# OpenPLCv0_2_0_USBSwitch.net
KiCad netlist of a schematic drawn in Altium Designer
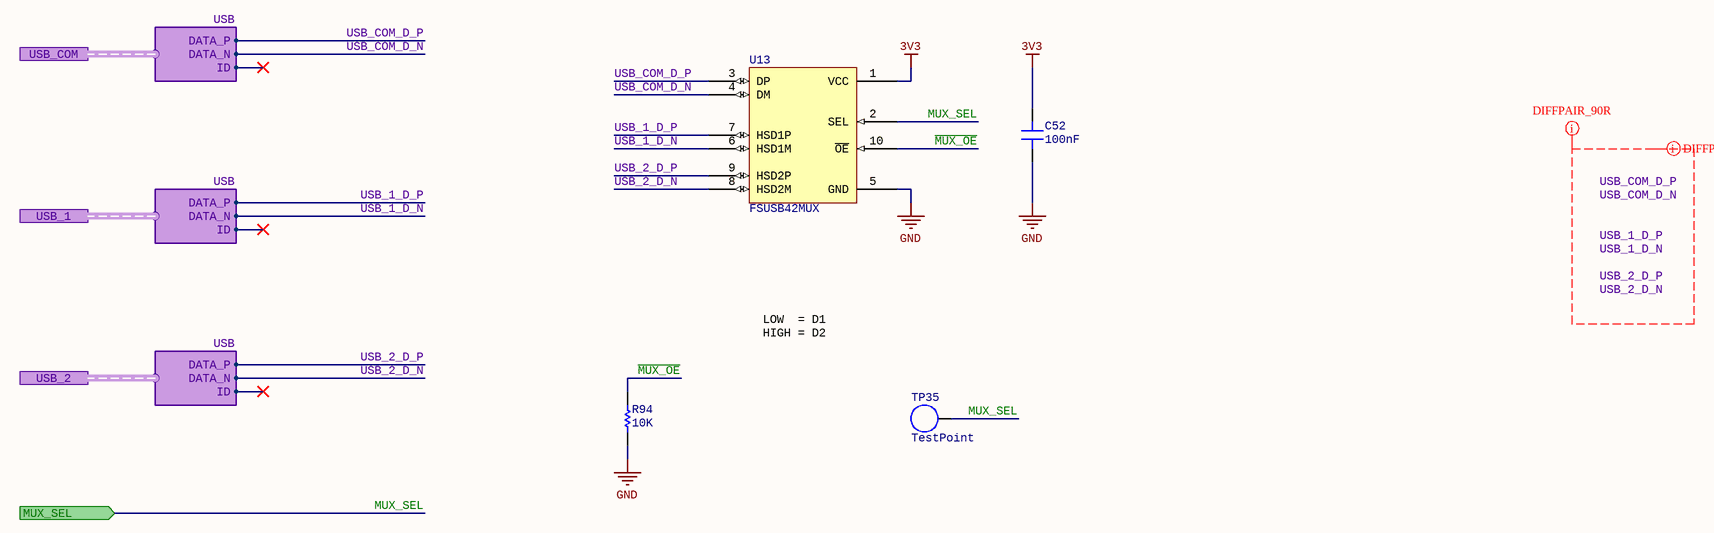
[diagram p0: OpenPLCv0.2.0_USBSwitch.SchDoc]

(export (version "E")
  (design (tool "Eeschema 10.0.6"))
  (components
    (comp (ref "C52")
      (value "CC0402KRX5R6BB104")
      (footprint "SMD_CAP_0402(1005)_N")
      (description "100nF ±10% 10V X5R 0402 Multilayer Ceramic Capacitors MLCC - SMD/SMT RoHS")
      (fields (field (name "TOLERANCE") "10%") (field (name "CAPACITANCE") "100nF"))
      (libsource (lib "BrauV2_Capacitor") (part "100nF 0402 10V 10%"))
    )
    (comp (ref "R94")
      (value "RC0402FR-0710KL")
      (footprint "SMD_RES_0402(1005)_N")
      (description "10kΩ ±1% 1/16W ±100ppm/℃ 0402 Chip Resistor - Surface Mount RoHS")
      (fields (field (name "TOLERANCE") "1%") (field (name "RESISTANCE") "10K"))
      (libsource (lib "BrauV2_Resistor") (part "10K 0402 1% 1/16W"))
    )
    (comp (ref "TP35")
      (value "TestPoint")
      (footprint "Pad")
      (libsource (lib "OpenPLCv0.2.0_Misc") (part "Test point"))
    )
    (comp (ref "U13")
      (value "FSUSB42MUX")
      (footprint "MSOP-10")
      (description "MSOP-10 USB ICs RoHS")
      (libsource (lib "BrauV2_IC") (part "FSUSB42MUX"))
    )
  )
  (nets
    (net (code "2") (name "/MUX_SEL") (class "Default")
      (node (ref "TP35") (pin "1") (pinfunction "1_1") (pintype "passive"))
      (node (ref "U13") (pin "2") (pinfunction "SEL_2") (pintype "input"))
    )
    (net (code "3") (name "/USB_1_D_N") (class "Default")
      (node (ref "U13") (pin "6") (pinfunction "HSD1M_6") (pintype "bidirectional"))
    )
    (net (code "4") (name "/USB_1_D_P") (class "Default")
      (node (ref "U13") (pin "7") (pinfunction "HSD1P_7") (pintype "bidirectional"))
    )
    (net (code "5") (name "/USB_2_D_N") (class "Default")
      (node (ref "U13") (pin "8") (pinfunction "HSD2M_8") (pintype "bidirectional"))
    )
    (net (code "6") (name "/USB_2_D_P") (class "Default")
      (node (ref "U13") (pin "9") (pinfunction "HSD2P_9") (pintype "bidirectional"))
    )
    (net (code "7") (name "/USB_COM_D_N") (class "Default")
      (node (ref "U13") (pin "4") (pinfunction "DM_4") (pintype "bidirectional"))
    )
    (net (code "8") (name "/USB_COM_D_P") (class "Default")
      (node (ref "U13") (pin "3") (pinfunction "DP_3") (pintype "bidirectional"))
    )
    (net (code "10") (name "/~{MUX_OE}") (class "Default")
      (node (ref "R94") (pin "2") (pinfunction "2_2") (pintype "passive"))
      (node (ref "U13") (pin "10") (pinfunction "~{OE}_10") (pintype "input"))
    )
    (net (code "11") (name "3V3") (class "Default")
      (node (ref "C52") (pin "2") (pinfunction "2_2") (pintype "passive"))
      (node (ref "U13") (pin "1") (pinfunction "VCC_1") (pintype "power_in"))
    )
    (net (code "12") (name "GND") (class "Default")
      (node (ref "C52") (pin "1") (pinfunction "1_1") (pintype "passive"))
      (node (ref "R94") (pin "1") (pinfunction "1_1") (pintype "passive"))
      (node (ref "U13") (pin "5") (pinfunction "GND_5") (pintype "power_in"))
    )
  )
)
